# Transmitter.net
KiCad netlist of a schematic drawn in Altium Designer
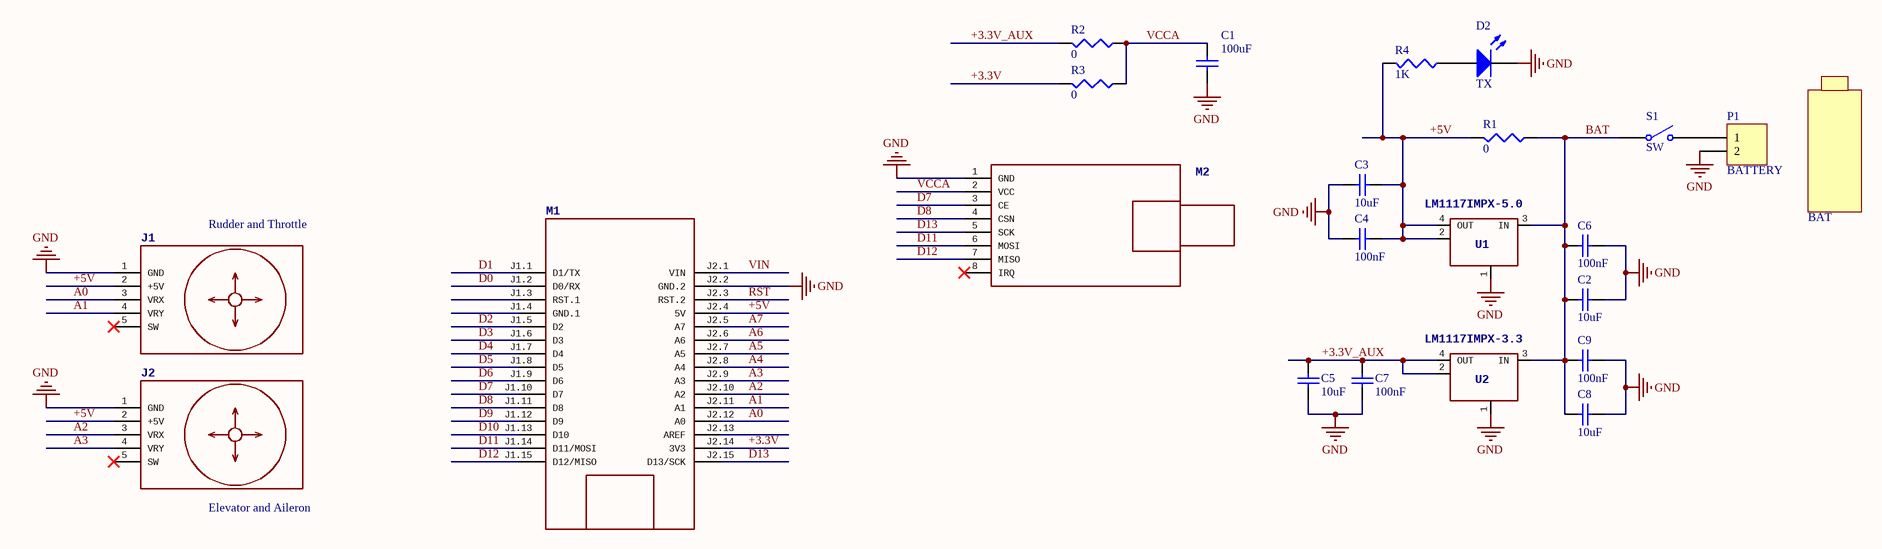
[diagram p0: Transmitter.SchDoc]

(export (version "E")
  (design (tool "Eeschema 10.0.6"))
  (components
    (comp (ref "BAT") (value "BAT") (footprint "BAT") (libsource (lib "Transmitter") (part "BAT")))
    (comp (ref "C1")
      (value "100uF")
      (footprint "CAPR5-4X5")
      (description "Capacitor")
      (fields (field (name "Comment") "Cap") (field (name "PUBLISHER") "Altium Limited"))
      (libsource (lib "Miscellaneous Devices") (part "Cap"))
    )
    (comp (ref "C2")
      (value "10uF")
      (footprint "R1206")
      (description "Capacitor")
      (fields (field (name "Comment") "Cap") (field (name "PUBLISHER") "Altium Limited"))
      (libsource (lib "Miscellaneous Devices") (part "Cap"))
    )
    (comp (ref "C3")
      (value "10uF")
      (footprint "R1206")
      (description "Capacitor")
      (fields (field (name "Comment") "Cap") (field (name "PUBLISHER") "Altium Limited"))
      (libsource (lib "Miscellaneous Devices") (part "Cap"))
    )
    (comp (ref "C4")
      (value "100nF")
      (footprint "R1206")
      (description "Capacitor")
      (fields (field (name "Comment") "Cap") (field (name "PUBLISHER") "Altium Limited"))
      (libsource (lib "Miscellaneous Devices") (part "Cap"))
    )
    (comp (ref "C5")
      (value "10uF")
      (footprint "R1206")
      (description "Capacitor")
      (fields (field (name "Comment") "Cap") (field (name "PUBLISHER") "Altium Limited"))
      (libsource (lib "Miscellaneous Devices") (part "Cap"))
    )
    (comp (ref "C6")
      (value "100nF")
      (footprint "R1206")
      (description "Capacitor")
      (fields (field (name "Comment") "Cap") (field (name "PUBLISHER") "Altium Limited"))
      (libsource (lib "Miscellaneous Devices") (part "Cap"))
    )
    (comp (ref "C7")
      (value "100nF")
      (footprint "R1206")
      (description "Capacitor")
      (fields (field (name "Comment") "Cap") (field (name "PUBLISHER") "Altium Limited"))
      (libsource (lib "Miscellaneous Devices") (part "Cap"))
    )
    (comp (ref "C8")
      (value "10uF")
      (footprint "R1206")
      (description "Capacitor")
      (fields (field (name "Comment") "Cap") (field (name "PUBLISHER") "Altium Limited"))
      (libsource (lib "Miscellaneous Devices") (part "Cap"))
    )
    (comp (ref "C9")
      (value "100nF")
      (footprint "R1206")
      (description "Capacitor")
      (fields (field (name "Comment") "Cap") (field (name "PUBLISHER") "Altium Limited"))
      (libsource (lib "Miscellaneous Devices") (part "Cap"))
    )
    (comp (ref "D2")
      (value "TX")
      (footprint "R1206")
      (description "Typical INFRARED GaAs LED")
      (fields (field (name "PUBLISHER") "Altium Limited"))
      (libsource (lib "Miscellaneous Devices") (part "LED0"))
    )
    (comp (ref "J1")
      (value "<b>2-Axis Analog Joystick</b> with Push Button\n<p>Tutorial is available here:<br />\n<a href=\"http://henrysbench.capnfatz.com/henrys-bench/arduino-sensors-and-input/arduino-ps2-joystick-tutorial-keyes-ky-023-deek-robot/\">http://henrysbench.capnfatz.com/henrys-bench/arduino-sensors-and-input/arduino-ps2-joystick-tutorial-keyes-ky-023-deek-robot/</a></p>\n<p><b><a href=\"http://www.ebay.com/sch/joystick+ps2+module\">Click here to find device on ebay.com</a></b></p>\n<p><img alt=\"photo\" src=\"http://www.diymodules.org/img/device-photo.php?name=JOYSTICK-2AXIS-BUTTON\"></p>")
      (footprint "JOYSTICK-2AXIS-BUTTON")
      (libsource (lib "diy-modules") (part "JOYSTICK-2AXIS-BUTTON"))
    )
    (comp (ref "J2")
      (value "<b>2-Axis Analog Joystick</b> with Push Button\n<p>Tutorial is available here:<br />\n<a href=\"http://henrysbench.capnfatz.com/henrys-bench/arduino-sensors-and-input/arduino-ps2-joystick-tutorial-keyes-ky-023-deek-robot/\">http://henrysbench.capnfatz.com/henrys-bench/arduino-sensors-and-input/arduino-ps2-joystick-tutorial-keyes-ky-023-deek-robot/</a></p>\n<p><b><a href=\"http://www.ebay.com/sch/joystick+ps2+module\">Click here to find device on ebay.com</a></b></p>\n<p><img alt=\"photo\" src=\"http://www.diymodules.org/img/device-photo.php?name=JOYSTICK-2AXIS-BUTTON\"></p>")
      (footprint "JOYSTICK-2AXIS-BUTTON")
      (libsource (lib "diy-modules") (part "JOYSTICK-2AXIS-BUTTON"))
    )
    (comp (ref "M1")
      (value "<b>Arduino Nano 3.0</b> and compatible devices\n<p>More details available here:<br>\n<a href=\"https://www.arduino.cc/en/Main/ArduinoBoardNano\">https://www.arduino.cc/en/Main/ArduinoBoardNano</a></p>\n<p><b><a href=\"http://www.ebay.com/sch/arduino+nano\">Click here to find device on ebay.com</a></b></p>\n\n<p><img alt=\"photo\" src=\"http://www.diymodules.org/img/device-photo.php?name=ARDUINO-NANO-3.0\"></p>")
      (footprint "ARDUINO-NANO-3.0")
      (libsource (lib "diy-modules") (part "ARDUINO-NANO-3.0"))
    )
    (comp (ref "M2")
      (value "<b>2.4 GHz Wireless Module</b> based on <b>NRF24L01</b> chip with preamplifier and external antenna\n<p><b><a href=\"http://www.ebay.com/sch/nrf24l01+pa+lna+sma\">Click here to find device on ebay.com</a></b></p>\n\n<p><img alt=\"photo\" src=\"http://www.diymodules.org/img/device-photo.php?name=WIRELESS-NRF24L01-PA-EXT\"></p>")
      (footprint "WIRELESS-NRF24L01-PA-EXT")
      (libsource (lib "diy-modules") (part "WIRELESS-NRF24L01-PA-EXT"))
    )
    (comp (ref "P1")
      (value "BATTERY")
      (footprint "HDR1X2")
      (description "Header, 2-Pin")
      (fields (field (name "PUBLISHER") "Altium Limited"))
      (libsource (lib "Miscellaneous Connectors") (part "Header 2"))
    )
    (comp (ref "R1")
      (value "0")
      (footprint "R1206")
      (description "RJ-1206-")
      (libsource (lib "TD1892_DUT_BOARD") (part "R_SM_1206"))
    )
    (comp (ref "R2")
      (value "0")
      (footprint "R1206")
      (description "RJ-1206-")
      (libsource (lib "TD1892_DUT_BOARD") (part "R_SM_1206"))
    )
    (comp (ref "R3")
      (value "0")
      (footprint "R1206")
      (description "RJ-1206-")
      (libsource (lib "TD1892_DUT_BOARD") (part "R_SM_1206"))
    )
    (comp (ref "R4")
      (value "1K")
      (footprint "R1206")
      (description "RJ-1206-")
      (libsource (lib "TD1892_DUT_BOARD") (part "R_SM_1206"))
    )
    (comp (ref "S1")
      (value "SW")
      (footprint "KEY")
      (description "Single-Pole, Single-Throw Switch")
      (fields (field (name "PUBLISHER") "Altium Limited"))
      (libsource (lib "Miscellaneous Devices") (part "SW-SPST"))
    )
    (comp (ref "U1")
      (value "LM1117IMPX-5.0")
      (footprint "LINEAR_SOT223")
      (description "Low-dropout linear regulator 5V  -LM1117IMPX-5.0")
      (libsource (lib "NanoV3.3") (part "0022_LM1117IMPX-5.0"))
    )
    (comp (ref "U2")
      (value "LM1117IMPX-3.3")
      (footprint "LINEAR_SOT223")
      (description "Low-dropout linear regulator 5V  -LM1117IMPX-5.0")
      (libsource (lib "NanoV3.3") (part "0022_LM1117IMPX-5.0"))
    )
  )
  (nets
    (net (code "1") (name "/+3.3V") (class "Default")
      (node (ref "M1") (pin "J2.14") (pinfunction "3V3_J2.14") (pintype "power_in"))
      (node (ref "R3") (pin "2") (pinfunction "2_2") (pintype "passive"))
    )
    (net (code "2") (name "/+3.3V_AUX") (class "Default")
      (node (ref "C5") (pin "1") (pinfunction "1_1") (pintype "passive"))
      (node (ref "C7") (pin "2") (pinfunction "2_2") (pintype "passive"))
      (node (ref "R2") (pin "2") (pinfunction "2_2") (pintype "passive"))
      (node (ref "U2") (pin "2") (pinfunction "OUT_2") (pintype "passive"))
      (node (ref "U2") (pin "4") (pinfunction "OUT_4") (pintype "passive"))
    )
    (net (code "3") (name "/+5V") (class "Default")
      (node (ref "C3") (pin "1") (pinfunction "1_1") (pintype "passive"))
      (node (ref "C4") (pin "1") (pinfunction "1_1") (pintype "passive"))
      (node (ref "J1") (pin "2") (pinfunction "+5V_2") (pintype "power_in"))
      (node (ref "J2") (pin "2") (pinfunction "+5V_2") (pintype "power_in"))
      (node (ref "M1") (pin "J2.4") (pinfunction "5V_J2.4") (pintype "power_in"))
      (node (ref "R1") (pin "2") (pinfunction "2_2") (pintype "passive"))
      (node (ref "R4") (pin "2") (pinfunction "2_2") (pintype "passive"))
      (node (ref "U1") (pin "2") (pinfunction "OUT_2") (pintype "passive"))
      (node (ref "U1") (pin "4") (pinfunction "OUT_4") (pintype "passive"))
    )
    (net (code "4") (name "/A0") (class "Default")
      (node (ref "J1") (pin "3") (pinfunction "VRX_3") (pintype "passive"))
      (node (ref "M1") (pin "J2.12") (pinfunction "A0_J2.12") (pintype "passive"))
    )
    (net (code "5") (name "/A1") (class "Default")
      (node (ref "J1") (pin "4") (pinfunction "VRY_4") (pintype "passive"))
      (node (ref "M1") (pin "J2.11") (pinfunction "A1_J2.11") (pintype "passive"))
    )
    (net (code "6") (name "/A2") (class "Default")
      (node (ref "J2") (pin "3") (pinfunction "VRX_3") (pintype "passive"))
      (node (ref "M1") (pin "J2.10") (pinfunction "A2_J2.10") (pintype "passive"))
    )
    (net (code "7") (name "/A3") (class "Default")
      (node (ref "J2") (pin "4") (pinfunction "VRY_4") (pintype "passive"))
      (node (ref "M1") (pin "J2.9") (pinfunction "A3_J2.9") (pintype "passive"))
    )
    (net (code "8") (name "/A4") (class "Default")
      (node (ref "M1") (pin "J2.8") (pinfunction "A4_J2.8") (pintype "passive"))
    )
    (net (code "9") (name "/A5") (class "Default")
      (node (ref "M1") (pin "J2.7") (pinfunction "A5_J2.7") (pintype "passive"))
    )
    (net (code "10") (name "/A6") (class "Default")
      (node (ref "M1") (pin "J2.6") (pinfunction "A6_J2.6") (pintype "passive"))
    )
    (net (code "11") (name "/A7") (class "Default")
      (node (ref "M1") (pin "J2.5") (pinfunction "A7_J2.5") (pintype "passive"))
    )
    (net (code "12") (name "/BAT") (class "Default")
      (node (ref "C2") (pin "1") (pinfunction "1_1") (pintype "passive"))
      (node (ref "C6") (pin "1") (pinfunction "1_1") (pintype "passive"))
      (node (ref "C8") (pin "2") (pinfunction "2_2") (pintype "passive"))
      (node (ref "C9") (pin "2") (pinfunction "2_2") (pintype "passive"))
      (node (ref "R1") (pin "1") (pinfunction "1_1") (pintype "passive"))
      (node (ref "S1") (pin "1") (pinfunction "COMMON_1") (pintype "passive"))
      (node (ref "U1") (pin "3") (pinfunction "IN_3") (pintype "passive"))
      (node (ref "U2") (pin "3") (pinfunction "IN_3") (pintype "passive"))
    )
    (net (code "13") (name "/D0") (class "Default")
      (node (ref "M1") (pin "J1.2") (pinfunction "D0/RX_J1.2") (pintype "passive"))
    )
    (net (code "14") (name "/D1") (class "Default")
      (node (ref "M1") (pin "J1.1") (pinfunction "D1/TX_J1.1") (pintype "passive"))
    )
    (net (code "15") (name "/D2") (class "Default")
      (node (ref "M1") (pin "J1.5") (pinfunction "D2_J1.5") (pintype "passive"))
    )
    (net (code "16") (name "/D3") (class "Default")
      (node (ref "M1") (pin "J1.6") (pinfunction "D3_J1.6") (pintype "passive"))
    )
    (net (code "17") (name "/D4") (class "Default")
      (node (ref "M1") (pin "J1.7") (pinfunction "D4_J1.7") (pintype "passive"))
    )
    (net (code "18") (name "/D5") (class "Default")
      (node (ref "M1") (pin "J1.8") (pinfunction "D5_J1.8") (pintype "passive"))
    )
    (net (code "19") (name "/D6") (class "Default")
      (node (ref "M1") (pin "J1.9") (pinfunction "D6_J1.9") (pintype "passive"))
    )
    (net (code "20") (name "/D7") (class "Default")
      (node (ref "M1") (pin "J1.10") (pinfunction "D7_J1.10") (pintype "passive"))
      (node (ref "M2") (pin "3") (pinfunction "CE_3") (pintype "passive"))
    )
    (net (code "21") (name "/D8") (class "Default")
      (node (ref "M1") (pin "J1.11") (pinfunction "D8_J1.11") (pintype "passive"))
      (node (ref "M2") (pin "4") (pinfunction "CSN_4") (pintype "passive"))
    )
    (net (code "22") (name "/D9") (class "Default")
      (node (ref "M1") (pin "J1.12") (pinfunction "D9_J1.12") (pintype "passive"))
    )
    (net (code "23") (name "/D10") (class "Default")
      (node (ref "M1") (pin "J1.13") (pinfunction "D10_J1.13") (pintype "passive"))
    )
    (net (code "24") (name "/D11") (class "Default")
      (node (ref "M1") (pin "J1.14") (pinfunction "D11/MOSI_J1.14") (pintype "passive"))
      (node (ref "M2") (pin "6") (pinfunction "MOSI_6") (pintype "passive"))
    )
    (net (code "25") (name "/D12") (class "Default")
      (node (ref "M1") (pin "J1.15") (pinfunction "D12/MISO_J1.15") (pintype "passive"))
      (node (ref "M2") (pin "7") (pinfunction "MISO_7") (pintype "passive"))
    )
    (net (code "26") (name "/D13") (class "Default")
      (node (ref "M1") (pin "J2.15") (pinfunction "D13/SCK_J2.15") (pintype "passive"))
      (node (ref "M2") (pin "5") (pinfunction "SCK_5") (pintype "passive"))
    )
    (net (code "27") (name "/RST") (class "Default")
      (node (ref "M1") (pin "J2.3") (pinfunction "RST.2_J2.3") (pintype "passive"))
    )
    (net (code "28") (name "/VCCA") (class "Default")
      (node (ref "C1") (pin "1") (pinfunction "1_1") (pintype "passive"))
      (node (ref "M2") (pin "2") (pinfunction "VCC_2") (pintype "power_in"))
      (node (ref "R2") (pin "1") (pinfunction "1_1") (pintype "passive"))
      (node (ref "R3") (pin "1") (pinfunction "1_1") (pintype "passive"))
    )
    (net (code "29") (name "/VIN") (class "Default")
      (node (ref "M1") (pin "J2.1") (pinfunction "VIN_J2.1") (pintype "power_in"))
    )
    (net (code "30") (name "GND") (class "Default")
      (node (ref "C1") (pin "2") (pinfunction "2_2") (pintype "passive"))
      (node (ref "C2") (pin "2") (pinfunction "2_2") (pintype "passive"))
      (node (ref "C3") (pin "2") (pinfunction "2_2") (pintype "passive"))
      (node (ref "C4") (pin "2") (pinfunction "2_2") (pintype "passive"))
      (node (ref "C5") (pin "2") (pinfunction "2_2") (pintype "passive"))
      (node (ref "C6") (pin "2") (pinfunction "2_2") (pintype "passive"))
      (node (ref "C7") (pin "1") (pinfunction "1_1") (pintype "passive"))
      (node (ref "C8") (pin "1") (pinfunction "1_1") (pintype "passive"))
      (node (ref "C9") (pin "1") (pinfunction "1_1") (pintype "passive"))
      (node (ref "D2") (pin "2") (pinfunction "K_2") (pintype "passive"))
      (node (ref "J1") (pin "1") (pinfunction "GND_1") (pintype "power_in"))
      (node (ref "J2") (pin "1") (pinfunction "GND_1") (pintype "power_in"))
      (node (ref "M1") (pin "J2.2") (pinfunction "GND.2_J2.2") (pintype "power_in"))
      (node (ref "M2") (pin "1") (pinfunction "GND_1") (pintype "power_in"))
      (node (ref "P1") (pin "2") (pinfunction "2_2") (pintype "passive"))
      (node (ref "U1") (pin "1") (pinfunction "GND/ADJ_1") (pintype "passive"))
      (node (ref "U2") (pin "1") (pinfunction "GND/ADJ_1") (pintype "passive"))
    )
    (net (code "31") (name "Net-(D2-A)") (class "Default")
      (node (ref "D2") (pin "1") (pinfunction "A_1") (pintype "passive"))
      (node (ref "R4") (pin "1") (pinfunction "1_1") (pintype "passive"))
    )
    (net (code "32") (name "Net-(S1-NO)") (class "Default")
      (node (ref "P1") (pin "1") (pinfunction "1_1") (pintype "passive"))
      (node (ref "S1") (pin "2") (pinfunction "NO_2") (pintype "passive"))
    )
    (net (code "33") (name "unconnected-(J1-SW-Pad5)") (class "Default")
      (node (ref "J1") (pin "5") (pinfunction "SW_5") (pintype "passive+no_connect"))
    )
    (net (code "34") (name "unconnected-(J2-SW-Pad5)") (class "Default")
      (node (ref "J2") (pin "5") (pinfunction "SW_5") (pintype "passive+no_connect"))
    )
    (net (code "35") (name "unconnected-(M1-AREF-PadJ2.13)") (class "Default")
      (node (ref "M1") (pin "J2.13") (pinfunction "AREF_J2.13") (pintype "passive"))
    )
    (net (code "36") (name "unconnected-(M1-GND.1-PadJ1.4)") (class "Default")
      (node (ref "M1") (pin "J1.4") (pinfunction "GND.1_J1.4") (pintype "power_in"))
    )
    (net (code "37") (name "unconnected-(M1-RST.1-PadJ1.3)") (class "Default")
      (node (ref "M1") (pin "J1.3") (pinfunction "RST.1_J1.3") (pintype "passive"))
    )
    (net (code "38") (name "unconnected-(M2-IRQ-Pad8)") (class "Default")
      (node (ref "M2") (pin "8") (pinfunction "IRQ_8") (pintype "passive+no_connect"))
    )
  )
)
